# 2__Ethernet_SDCard.net
KiCad netlist of a schematic drawn in Altium Designer
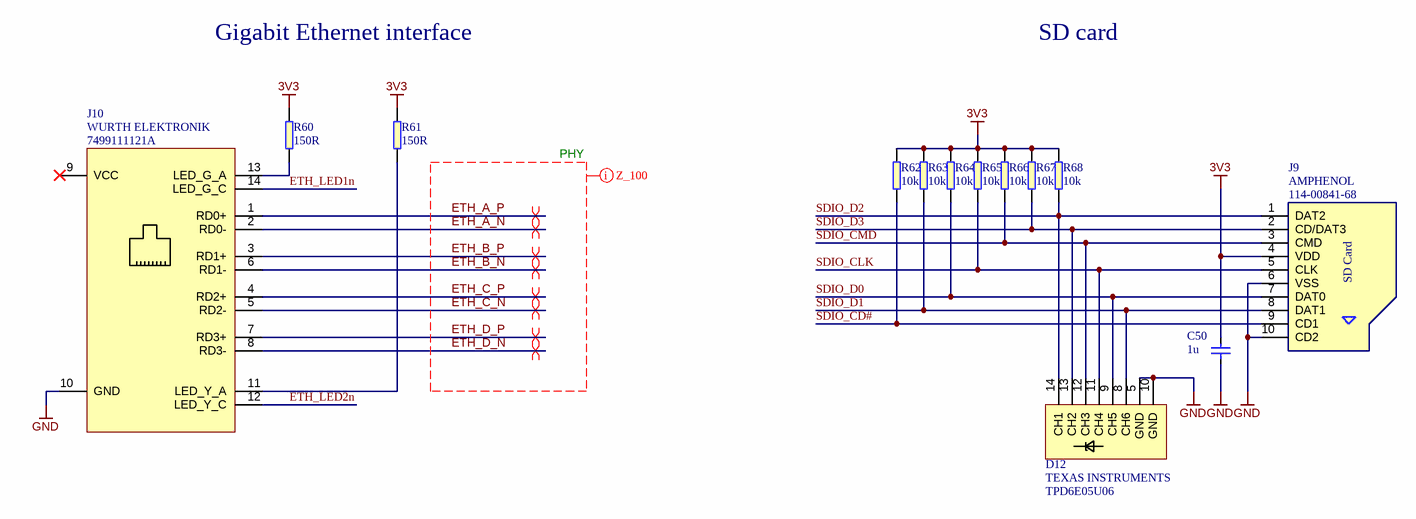
[diagram p0: [2]_Ethernet_SDCard.SchDoc]

(export (version "E")
  (design (tool "Eeschema 10.0.6"))
  (components
    (comp (ref "C50")
      (value "1u")
      (footprint "0603")
      (description "MLCC SMT Capacitor 1u 0603")
      (fields (field (name "PART NUMBER") "C_1u_0603") (field (name "MANUFACTURER") "MULTICOMP"))
      (libsource (lib "Zynq-Video-Board-Rev-1.2") (part "C_1u_0603"))
    )
    (comp (ref "D12")
      (value "TPD6E05U06")
      (footprint "TPD6E05U06_PASS")
      (description "ESD Suppressors 6-CH Pass through layout")
      (fields
        (field (name "PART NUMBER") "TPD6E05U06_PASS")
        (field (name "MANUFACTURER") "TEXAS INSTRUMENTS")
      )
      (libsource (lib "Zynq-Video-Board-Rev-1.2") (part "TPD6E05U06"))
    )
    (comp (ref "J9")
      (value "114-00841-68")
      (footprint "114-00841-68")
      (description "Micro SD card holder")
      (fields (field (name "PART NUMBER") "AMP-114-00841-68") (field (name "MANUFACTURER") "AMPHENOL"))
      (libsource (lib "Zynq-Video-Board-Rev-1.2") (part "Micro_SD"))
    )
    (comp (ref "J10")
      (value "7499111121A")
      (footprint "WE_7499111121A")
      (description "CONN MAGJACK 1PORT 1000 BASE-T")
      (fields (field (name "PART NUMBER") "WE_7499111121A") (field (name "MANUFACTURER") "WURTH ELEKTRONIK"))
      (libsource (lib "Zynq-Video-Board-Rev-1.2") (part "WE_7499111121A"))
    )
    (comp (ref "R60")
      (value "150R")
      (footprint "0402")
      (description "SMT Resistor 150R_0402")
      (fields (field (name "PART NUMBER") "R_150R_0402") (field (name "TOLERANCE") "1%"))
      (libsource (lib "Zynq-Video-Board-Rev-1.2") (part "R_150R_0402"))
    )
    (comp (ref "R61")
      (value "150R")
      (footprint "0402")
      (description "SMT Resistor 150R_0402")
      (fields (field (name "PART NUMBER") "R_150R_0402") (field (name "TOLERANCE") "1%"))
      (libsource (lib "Zynq-Video-Board-Rev-1.2") (part "R_150R_0402"))
    )
    (comp (ref "R62")
      (value "10k")
      (footprint "0402")
      (description "SMT Resistor 10k 0402")
      (fields (field (name "PART NUMBER") "R_10k_0402") (field (name "TOLERANCE") "1%"))
      (libsource (lib "Zynq-Video-Board-Rev-1.2") (part "R_10k_0402"))
    )
    (comp (ref "R63")
      (value "10k")
      (footprint "0402")
      (description "SMT Resistor 10k 0402")
      (fields (field (name "PART NUMBER") "R_10k_0402") (field (name "TOLERANCE") "1%"))
      (libsource (lib "Zynq-Video-Board-Rev-1.2") (part "R_10k_0402"))
    )
    (comp (ref "R64")
      (value "10k")
      (footprint "0402")
      (description "SMT Resistor 10k 0402")
      (fields (field (name "PART NUMBER") "R_10k_0402") (field (name "TOLERANCE") "1%"))
      (libsource (lib "Zynq-Video-Board-Rev-1.2") (part "R_10k_0402"))
    )
    (comp (ref "R65")
      (value "10k")
      (footprint "0402")
      (description "SMT Resistor 10k 0402")
      (fields (field (name "PART NUMBER") "R_10k_0402") (field (name "TOLERANCE") "1%"))
      (libsource (lib "Zynq-Video-Board-Rev-1.2") (part "R_10k_0402"))
    )
    (comp (ref "R66")
      (value "10k")
      (footprint "0402")
      (description "SMT Resistor 10k 0402")
      (fields (field (name "PART NUMBER") "R_10k_0402") (field (name "TOLERANCE") "1%"))
      (libsource (lib "Zynq-Video-Board-Rev-1.2") (part "R_10k_0402"))
    )
    (comp (ref "R67")
      (value "10k")
      (footprint "0402")
      (description "SMT Resistor 10k 0402")
      (fields (field (name "PART NUMBER") "R_10k_0402") (field (name "TOLERANCE") "1%"))
      (libsource (lib "Zynq-Video-Board-Rev-1.2") (part "R_10k_0402"))
    )
    (comp (ref "R68")
      (value "10k")
      (footprint "0402")
      (description "SMT Resistor 10k 0402")
      (fields (field (name "PART NUMBER") "R_10k_0402") (field (name "TOLERANCE") "1%"))
      (libsource (lib "Zynq-Video-Board-Rev-1.2") (part "R_10k_0402"))
    )
  )
  (nets
    (net (code "1") (name "/ETH_A_N") (class "Default")
      (node (ref "J10") (pin "2") (pinfunction "RD0-_2") (pintype "passive"))
    )
    (net (code "2") (name "/ETH_A_P") (class "Default")
      (node (ref "J10") (pin "1") (pinfunction "RD0+_1") (pintype "passive"))
    )
    (net (code "3") (name "/ETH_B_N") (class "Default")
      (node (ref "J10") (pin "6") (pinfunction "RD1-_6") (pintype "passive"))
    )
    (net (code "4") (name "/ETH_B_P") (class "Default")
      (node (ref "J10") (pin "3") (pinfunction "RD1+_3") (pintype "passive"))
    )
    (net (code "5") (name "/ETH_C_N") (class "Default")
      (node (ref "J10") (pin "5") (pinfunction "RD2-_5") (pintype "passive"))
    )
    (net (code "6") (name "/ETH_C_P") (class "Default")
      (node (ref "J10") (pin "4") (pinfunction "RD2+_4") (pintype "passive"))
    )
    (net (code "7") (name "/ETH_D_N") (class "Default")
      (node (ref "J10") (pin "8") (pinfunction "RD3-_8") (pintype "passive"))
    )
    (net (code "8") (name "/ETH_D_P") (class "Default")
      (node (ref "J10") (pin "7") (pinfunction "RD3+_7") (pintype "passive"))
    )
    (net (code "9") (name "/ETH_LED1n") (class "Default")
      (node (ref "J10") (pin "14") (pinfunction "LED_G_C_14") (pintype "passive"))
    )
    (net (code "10") (name "/ETH_LED2n") (class "Default")
      (node (ref "J10") (pin "12") (pinfunction "LED_Y_C_12") (pintype "passive"))
    )
    (net (code "11") (name "/SDIO_CD#") (class "Default")
      (node (ref "J9") (pin "9") (pinfunction "CD1_9") (pintype "passive"))
      (node (ref "R62") (pin "1") (pintype "passive"))
    )
    (net (code "12") (name "/SDIO_CLK") (class "Default")
      (node (ref "D12") (pin "11") (pinfunction "CH4_11") (pintype "passive"))
      (node (ref "J9") (pin "5") (pinfunction "CLK_5") (pintype "passive"))
      (node (ref "R65") (pin "1") (pintype "passive"))
    )
    (net (code "13") (name "/SDIO_CMD") (class "Default")
      (node (ref "D12") (pin "12") (pinfunction "CH3_12") (pintype "passive"))
      (node (ref "J9") (pin "3") (pinfunction "CMD_3") (pintype "passive"))
      (node (ref "R66") (pin "1") (pintype "passive"))
    )
    (net (code "14") (name "/SDIO_D0") (class "Default")
      (node (ref "D12") (pin "9") (pinfunction "CH5_9") (pintype "passive"))
      (node (ref "J9") (pin "7") (pinfunction "DAT0_7") (pintype "passive"))
      (node (ref "R64") (pin "1") (pintype "passive"))
    )
    (net (code "15") (name "/SDIO_D1") (class "Default")
      (node (ref "D12") (pin "8") (pinfunction "CH6_8") (pintype "passive"))
      (node (ref "J9") (pin "8") (pinfunction "DAT1_8") (pintype "passive"))
      (node (ref "R63") (pin "1") (pintype "passive"))
    )
    (net (code "16") (name "/SDIO_D2") (class "Default")
      (node (ref "D12") (pin "14") (pinfunction "CH1_14") (pintype "passive"))
      (node (ref "J9") (pin "1") (pinfunction "DAT2_1") (pintype "passive"))
      (node (ref "R68") (pin "1") (pintype "passive"))
    )
    (net (code "17") (name "/SDIO_D3") (class "Default")
      (node (ref "D12") (pin "13") (pinfunction "CH2_13") (pintype "passive"))
      (node (ref "J9") (pin "2") (pinfunction "CD/DAT3_2") (pintype "passive"))
      (node (ref "R67") (pin "1") (pintype "passive"))
    )
    (net (code "18") (name "3V3") (class "Default")
      (node (ref "C50") (pin "2") (pinfunction "2_2") (pintype "passive"))
      (node (ref "J9") (pin "4") (pinfunction "VDD_4") (pintype "passive"))
      (node (ref "R60") (pin "2") (pintype "passive"))
      (node (ref "R61") (pin "2") (pintype "passive"))
      (node (ref "R62") (pin "2") (pintype "passive"))
      (node (ref "R63") (pin "2") (pintype "passive"))
      (node (ref "R64") (pin "2") (pintype "passive"))
      (node (ref "R65") (pin "2") (pintype "passive"))
      (node (ref "R66") (pin "2") (pintype "passive"))
      (node (ref "R67") (pin "2") (pintype "passive"))
      (node (ref "R68") (pin "2") (pintype "passive"))
    )
    (net (code "19") (name "GND") (class "Default")
      (node (ref "C50") (pin "1") (pinfunction "1_1") (pintype "passive"))
      (node (ref "D12") (pin "10") (pinfunction "GND_10") (pintype "passive"))
      (node (ref "D12") (pin "5") (pinfunction "GND_5") (pintype "passive"))
      (node (ref "J10") (pin "10") (pinfunction "GND_10") (pintype "passive"))
      (node (ref "J9") (pin "10") (pinfunction "CD2_10") (pintype "passive"))
      (node (ref "J9") (pin "6") (pinfunction "VSS_6") (pintype "passive"))
    )
    (net (code "20") (name "Net-(J10-LED_G_A)") (class "Default")
      (node (ref "J10") (pin "13") (pinfunction "LED_G_A_13") (pintype "passive"))
      (node (ref "R60") (pin "1") (pintype "passive"))
    )
    (net (code "21") (name "Net-(J10-LED_Y_A)") (class "Default")
      (node (ref "J10") (pin "11") (pinfunction "LED_Y_A_11") (pintype "passive"))
      (node (ref "R61") (pin "1") (pintype "passive"))
    )
    (net (code "22") (name "unconnected-(J10-VCC-Pad9)") (class "Default")
      (node (ref "J10") (pin "9") (pinfunction "VCC_9") (pintype "passive+no_connect"))
    )
  )
)
